# EPOLY.net
KiCad netlist of a schematic drawn in Altium Designer
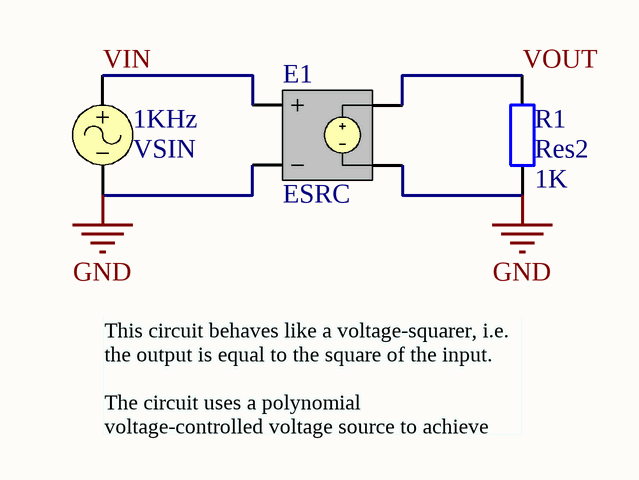
[diagram p0: EPOLY.SCHDOC]

(export (version "E")
  (design (tool "Eeschema 10.0.6"))
  (components
    (comp (ref "1KHz")
      (value "VSIN")
      (description "Sinusoidal Voltage Source")
      (fields (field (name "PUBLISHER") "Altium Limited"))
      (libsource (lib "Simulation Sources") (part "VSIN"))
    )
    (comp (ref "E1")
      (value "ESRC")
      (description "Voltage Controlled Voltage Source")
      (fields (field (name "PUBLISHER") "Altium Limited"))
      (libsource (lib "Simulation Sources") (part "ESRC"))
    )
    (comp (ref "R1")
      (value "Res2")
      (footprint "AXIAL-0.4")
      (description "Resistor")
      (fields (field (name "ALTIUM_VALUE") "1K") (field (name "PUBLISHER") "Altium Limited"))
      (libsource (lib "Miscellaneous Devices") (part "Res2"))
    )
  )
  (nets
    (net (code "1") (name "/VIN") (class "Default")
      (node (ref "1KHz") (pin "1") (pinfunction "1_1") (pintype "passive"))
      (node (ref "E1") (pin "1") (pinfunction "NC+_1") (pintype "passive"))
    )
    (net (code "2") (name "/VOUT") (class "Default")
      (node (ref "E1") (pin "3") (pinfunction "N+_3") (pintype "passive"))
      (node (ref "R1") (pin "2") (pinfunction "2_2") (pintype "passive"))
    )
    (net (code "3") (name "GND") (class "Default")
      (node (ref "1KHz") (pin "2") (pinfunction "2_2") (pintype "passive"))
      (node (ref "E1") (pin "2") (pinfunction "NC-_2") (pintype "passive"))
      (node (ref "E1") (pin "4") (pinfunction "N-_4") (pintype "passive"))
      (node (ref "R1") (pin "1") (pinfunction "1_1") (pintype "passive"))
    )
  )
)
